# color-spu-strip-1_1-1019.net
KiCad netlist of a schematic drawn in EasyEDA Pro
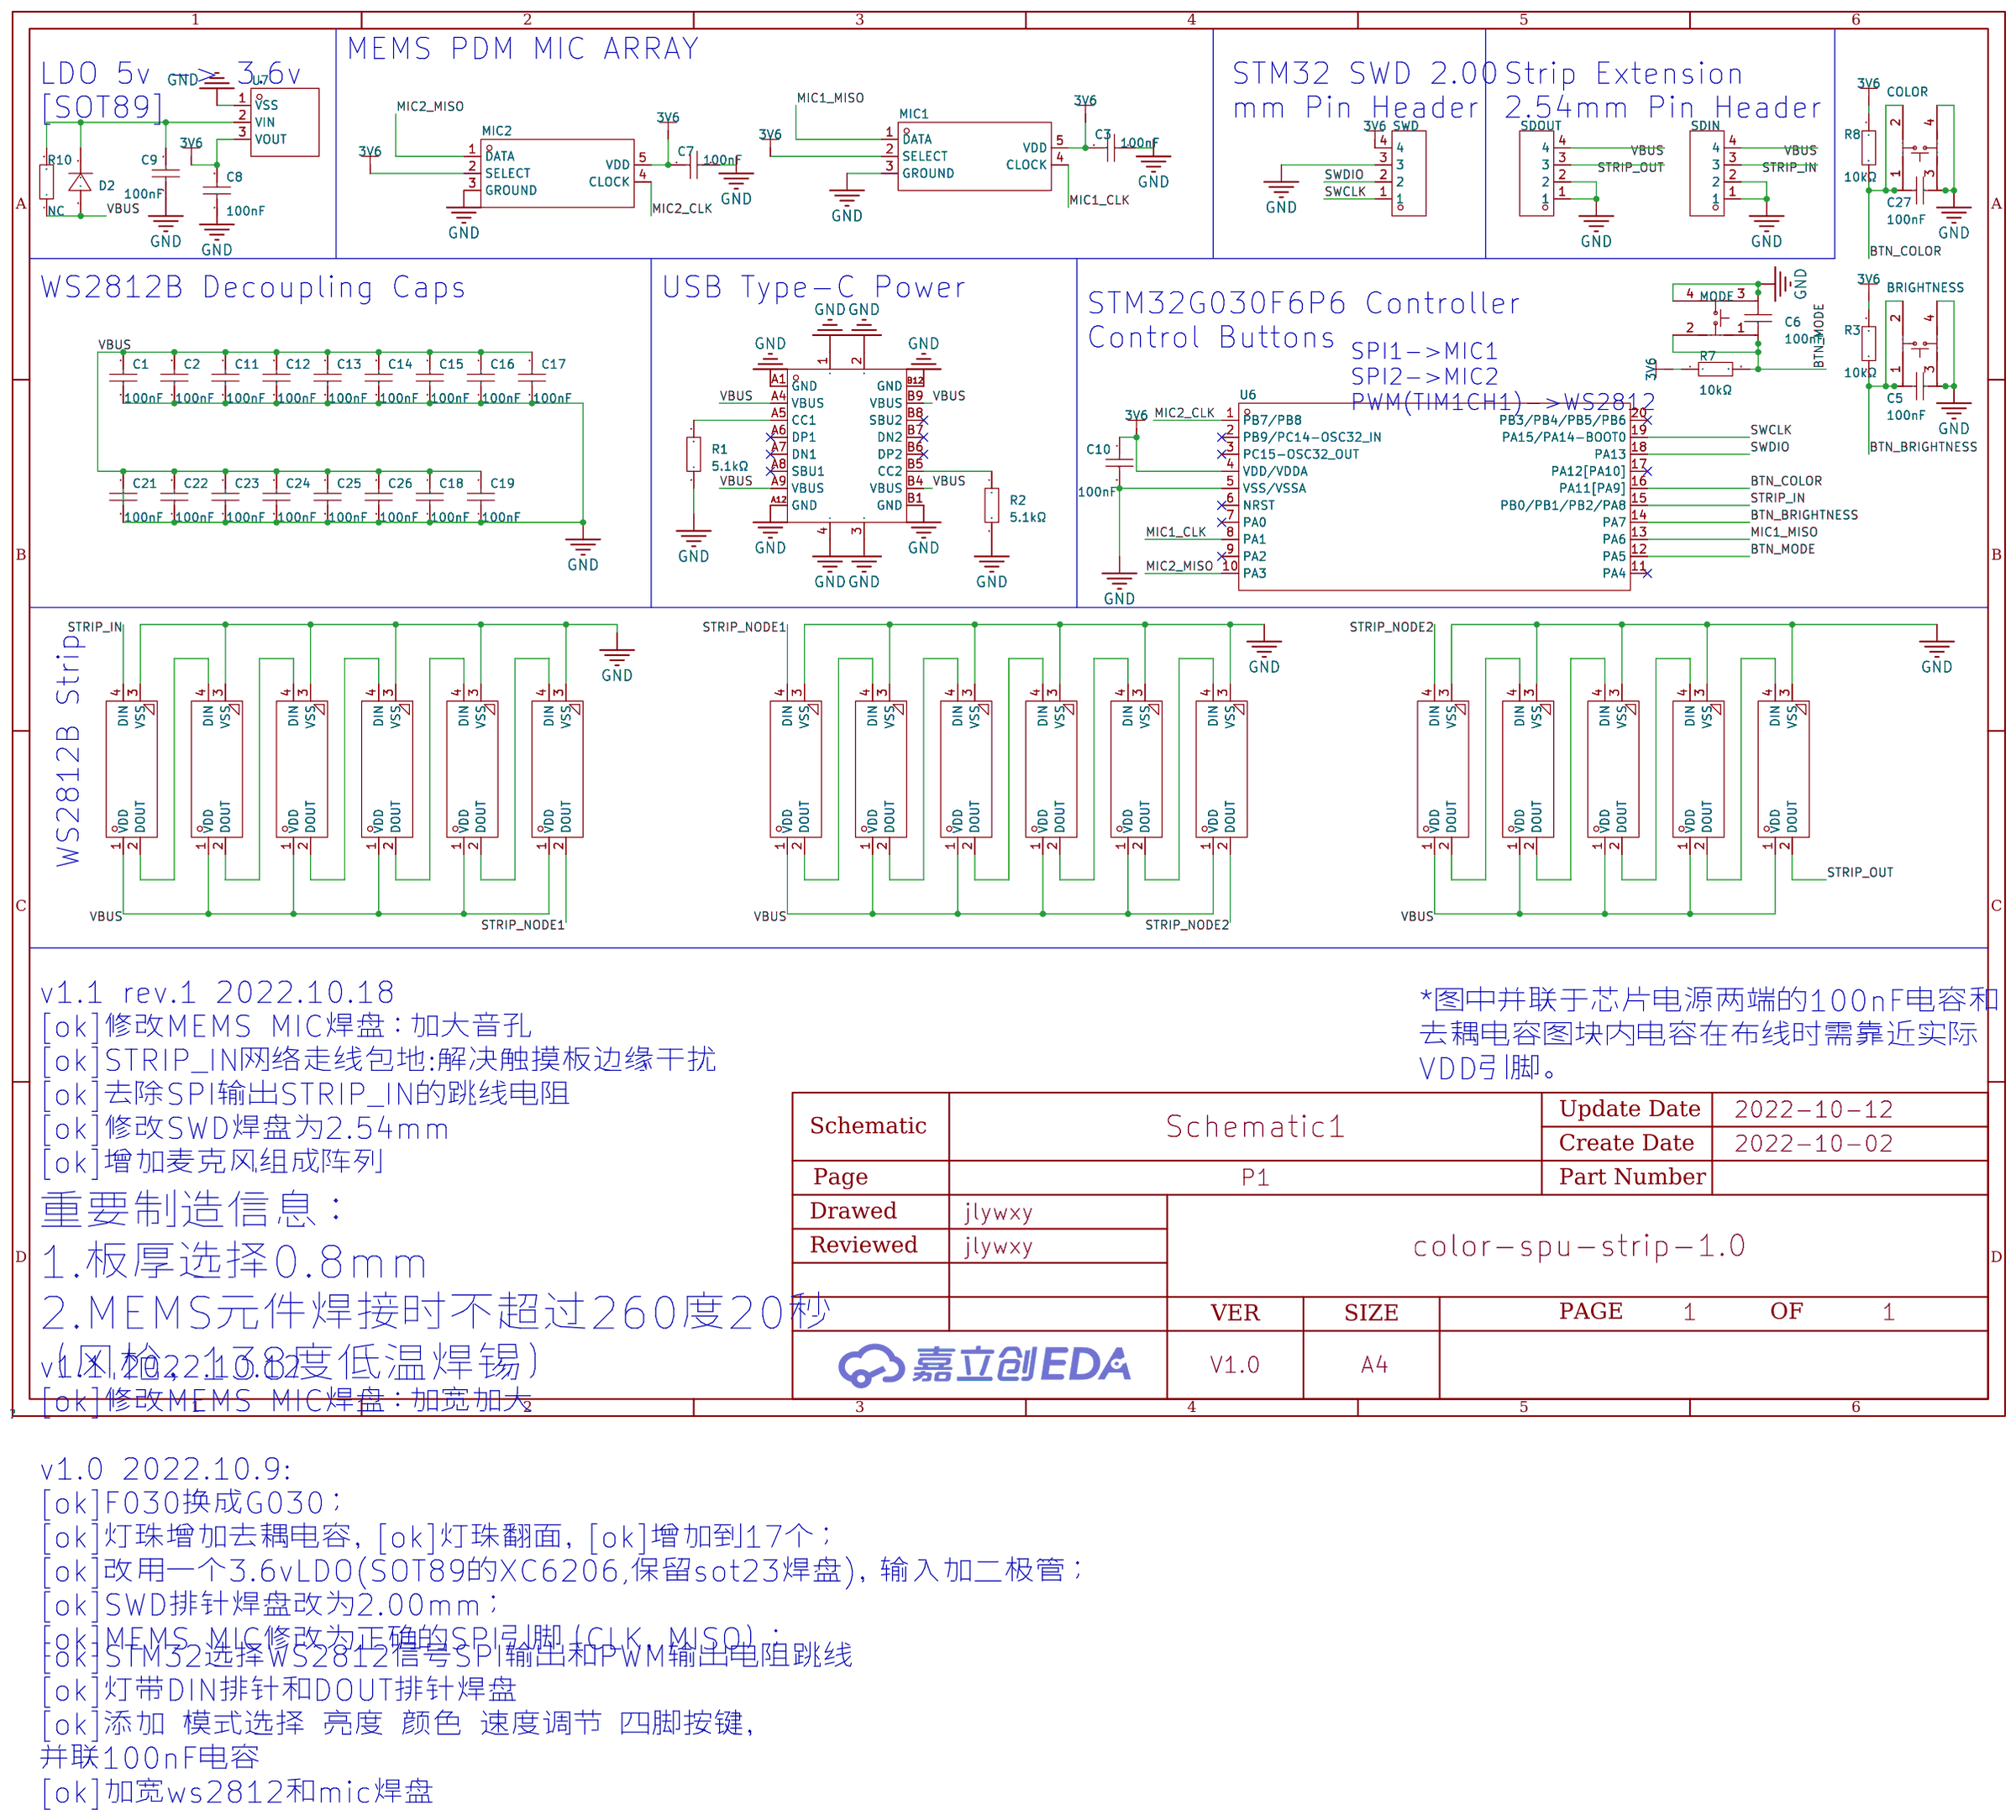
[diagram p0: schematic sheet]

(export (version "E")
  (design (tool "Eeschema 10.0.6"))
  (components
    (comp (ref "BRIGHTNESS")
      (value "SKRPABE010")
      (footprint "easyedapro:KEY-SMD_4P-L4.2-W3.2-P2.20-LS4.6")
      (description "触点电流:50mA;额定电压(DC):16V;电路结构:单刀单掷;安装方式:立贴;按钮形状:椭圆形按钮;带灯:-;开关长度:4.2mm;开关宽度:3.2mm;开关高度:2.5mm;")
      (fields (field (name "Manufacturer") "ALPSALPINE(阿尔卑斯阿尔派)"))
      (libsource (lib "easyedapro") (part "SKRPABE010"))
    )
    (comp (ref "C1")
      (value "100nF")
      (footprint "easyedapro:C0402")
      (description "容值:1uF;精度:±10%;额定电压:10V;材质(温度系数):X5R;")
      (fields
        (field (name "Manufacturer Part") "CL05A105KP5NNNC")
        (field (name "Manufacturer") "SAMSUNG(三星)")
      )
      (libsource (lib "easyedapro") (part "CL05A105KP5NNNC"))
    )
    (comp (ref "C2")
      (value "100nF")
      (footprint "easyedapro:C0402")
      (description "容值:1uF;精度:±10%;额定电压:10V;材质(温度系数):X5R;")
      (fields
        (field (name "Manufacturer Part") "CL05A105KP5NNNC")
        (field (name "Manufacturer") "SAMSUNG(三星)")
      )
      (libsource (lib "easyedapro") (part "CL05A105KP5NNNC"))
    )
    (comp (ref "C3")
      (value "100nF")
      (footprint "easyedapro:C0402")
      (description "容值:1uF;精度:±10%;额定电压:10V;材质(温度系数):X5R;")
      (fields
        (field (name "Manufacturer Part") "CL05A105KP5NNNC")
        (field (name "Manufacturer") "SAMSUNG(三星)")
      )
      (libsource (lib "easyedapro") (part "CL05A105KP5NNNC"))
    )
    (comp (ref "C5")
      (value "100nF")
      (footprint "easyedapro:C0402")
      (description "容值:1uF;精度:±10%;额定电压:10V;材质(温度系数):X5R;")
      (fields
        (field (name "Manufacturer Part") "CL05A105KP5NNNC")
        (field (name "Manufacturer") "SAMSUNG(三星)")
      )
      (libsource (lib "easyedapro") (part "CL05A105KP5NNNC"))
    )
    (comp (ref "C6")
      (value "100nF")
      (footprint "easyedapro:C0402")
      (description "容值:1uF;精度:±10%;额定电压:10V;材质(温度系数):X5R;")
      (fields
        (field (name "Manufacturer Part") "CL05A105KP5NNNC")
        (field (name "Manufacturer") "SAMSUNG(三星)")
      )
      (libsource (lib "easyedapro") (part "CL05A105KP5NNNC"))
    )
    (comp (ref "C7")
      (value "100nF")
      (footprint "easyedapro:C0402")
      (description "容值:1uF;精度:±10%;额定电压:10V;材质(温度系数):X5R;")
      (fields
        (field (name "Manufacturer Part") "CL05A105KP5NNNC")
        (field (name "Manufacturer") "SAMSUNG(三星)")
      )
      (libsource (lib "easyedapro") (part "CL05A105KP5NNNC"))
    )
    (comp (ref "C8")
      (value "100nF")
      (footprint "easyedapro:C0402")
      (description "容值:1uF;精度:±10%;额定电压:10V;材质(温度系数):X5R;")
      (fields
        (field (name "Manufacturer Part") "CL05A105KP5NNNC")
        (field (name "Manufacturer") "SAMSUNG(三星)")
      )
      (libsource (lib "easyedapro") (part "CL05A105KP5NNNC"))
    )
    (comp (ref "C9")
      (value "100nF")
      (footprint "easyedapro:C0402")
      (description "容值:1uF;精度:±10%;额定电压:10V;材质(温度系数):X5R;")
      (fields
        (field (name "Manufacturer Part") "CL05A105KP5NNNC")
        (field (name "Manufacturer") "SAMSUNG(三星)")
      )
      (libsource (lib "easyedapro") (part "CL05A105KP5NNNC"))
    )
    (comp (ref "C10")
      (value "100nF")
      (footprint "easyedapro:C0402")
      (description "容值:1uF;精度:±10%;额定电压:10V;材质(温度系数):X5R;")
      (fields
        (field (name "Manufacturer Part") "CL05A105KP5NNNC")
        (field (name "Manufacturer") "SAMSUNG(三星)")
      )
      (libsource (lib "easyedapro") (part "CL05A105KP5NNNC"))
    )
    (comp (ref "C11")
      (value "100nF")
      (footprint "easyedapro:C0402")
      (description "容值:1uF;精度:±10%;额定电压:10V;材质(温度系数):X5R;")
      (fields
        (field (name "Manufacturer Part") "CL05A105KP5NNNC")
        (field (name "Manufacturer") "SAMSUNG(三星)")
      )
      (libsource (lib "easyedapro") (part "CL05A105KP5NNNC"))
    )
    (comp (ref "C12")
      (value "100nF")
      (footprint "easyedapro:C0402")
      (description "容值:1uF;精度:±10%;额定电压:10V;材质(温度系数):X5R;")
      (fields
        (field (name "Manufacturer Part") "CL05A105KP5NNNC")
        (field (name "Manufacturer") "SAMSUNG(三星)")
      )
      (libsource (lib "easyedapro") (part "CL05A105KP5NNNC"))
    )
    (comp (ref "C13")
      (value "100nF")
      (footprint "easyedapro:C0402")
      (description "容值:1uF;精度:±10%;额定电压:10V;材质(温度系数):X5R;")
      (fields
        (field (name "Manufacturer Part") "CL05A105KP5NNNC")
        (field (name "Manufacturer") "SAMSUNG(三星)")
      )
      (libsource (lib "easyedapro") (part "CL05A105KP5NNNC"))
    )
    (comp (ref "C14")
      (value "100nF")
      (footprint "easyedapro:C0402")
      (description "容值:1uF;精度:±10%;额定电压:10V;材质(温度系数):X5R;")
      (fields
        (field (name "Manufacturer Part") "CL05A105KP5NNNC")
        (field (name "Manufacturer") "SAMSUNG(三星)")
      )
      (libsource (lib "easyedapro") (part "CL05A105KP5NNNC"))
    )
    (comp (ref "C15")
      (value "100nF")
      (footprint "easyedapro:C0402")
      (description "容值:1uF;精度:±10%;额定电压:10V;材质(温度系数):X5R;")
      (fields
        (field (name "Manufacturer Part") "CL05A105KP5NNNC")
        (field (name "Manufacturer") "SAMSUNG(三星)")
      )
      (libsource (lib "easyedapro") (part "CL05A105KP5NNNC"))
    )
    (comp (ref "C16")
      (value "100nF")
      (footprint "easyedapro:C0402")
      (description "容值:1uF;精度:±10%;额定电压:10V;材质(温度系数):X5R;")
      (fields
        (field (name "Manufacturer Part") "CL05A105KP5NNNC")
        (field (name "Manufacturer") "SAMSUNG(三星)")
      )
      (libsource (lib "easyedapro") (part "CL05A105KP5NNNC"))
    )
    (comp (ref "C17")
      (value "100nF")
      (footprint "easyedapro:C0402")
      (description "容值:1uF;精度:±10%;额定电压:10V;材质(温度系数):X5R;")
      (fields
        (field (name "Manufacturer Part") "CL05A105KP5NNNC")
        (field (name "Manufacturer") "SAMSUNG(三星)")
      )
      (libsource (lib "easyedapro") (part "CL05A105KP5NNNC"))
    )
    (comp (ref "C18")
      (value "100nF")
      (footprint "easyedapro:C0402")
      (description "容值:1uF;精度:±10%;额定电压:10V;材质(温度系数):X5R;")
      (fields
        (field (name "Manufacturer Part") "CL05A105KP5NNNC")
        (field (name "Manufacturer") "SAMSUNG(三星)")
      )
      (libsource (lib "easyedapro") (part "CL05A105KP5NNNC"))
    )
    (comp (ref "C19")
      (value "100nF")
      (footprint "easyedapro:C0402")
      (description "容值:1uF;精度:±10%;额定电压:10V;材质(温度系数):X5R;")
      (fields
        (field (name "Manufacturer Part") "CL05A105KP5NNNC")
        (field (name "Manufacturer") "SAMSUNG(三星)")
      )
      (libsource (lib "easyedapro") (part "CL05A105KP5NNNC"))
    )
    (comp (ref "C21")
      (value "100nF")
      (footprint "easyedapro:C0402")
      (description "容值:1uF;精度:±10%;额定电压:10V;材质(温度系数):X5R;")
      (fields
        (field (name "Manufacturer Part") "CL05A105KP5NNNC")
        (field (name "Manufacturer") "SAMSUNG(三星)")
      )
      (libsource (lib "easyedapro") (part "CL05A105KP5NNNC"))
    )
    (comp (ref "C22")
      (value "100nF")
      (footprint "easyedapro:C0402")
      (description "容值:1uF;精度:±10%;额定电压:10V;材质(温度系数):X5R;")
      (fields
        (field (name "Manufacturer Part") "CL05A105KP5NNNC")
        (field (name "Manufacturer") "SAMSUNG(三星)")
      )
      (libsource (lib "easyedapro") (part "CL05A105KP5NNNC"))
    )
    (comp (ref "C23")
      (value "100nF")
      (footprint "easyedapro:C0402")
      (description "容值:1uF;精度:±10%;额定电压:10V;材质(温度系数):X5R;")
      (fields
        (field (name "Manufacturer Part") "CL05A105KP5NNNC")
        (field (name "Manufacturer") "SAMSUNG(三星)")
      )
      (libsource (lib "easyedapro") (part "CL05A105KP5NNNC"))
    )
    (comp (ref "C24")
      (value "100nF")
      (footprint "easyedapro:C0402")
      (description "容值:1uF;精度:±10%;额定电压:10V;材质(温度系数):X5R;")
      (fields
        (field (name "Manufacturer Part") "CL05A105KP5NNNC")
        (field (name "Manufacturer") "SAMSUNG(三星)")
      )
      (libsource (lib "easyedapro") (part "CL05A105KP5NNNC"))
    )
    (comp (ref "C25")
      (value "100nF")
      (footprint "easyedapro:C0402")
      (description "容值:1uF;精度:±10%;额定电压:10V;材质(温度系数):X5R;")
      (fields
        (field (name "Manufacturer Part") "CL05A105KP5NNNC")
        (field (name "Manufacturer") "SAMSUNG(三星)")
      )
      (libsource (lib "easyedapro") (part "CL05A105KP5NNNC"))
    )
    (comp (ref "C26")
      (value "100nF")
      (footprint "easyedapro:C0402")
      (description "容值:1uF;精度:±10%;额定电压:10V;材质(温度系数):X5R;")
      (fields
        (field (name "Manufacturer Part") "CL05A105KP5NNNC")
        (field (name "Manufacturer") "SAMSUNG(三星)")
      )
      (libsource (lib "easyedapro") (part "CL05A105KP5NNNC"))
    )
    (comp (ref "C27")
      (value "100nF")
      (footprint "easyedapro:C0402")
      (description "容值:1uF;精度:±10%;额定电压:10V;材质(温度系数):X5R;")
      (fields
        (field (name "Manufacturer Part") "CL05A105KP5NNNC")
        (field (name "Manufacturer") "SAMSUNG(三星)")
      )
      (libsource (lib "easyedapro") (part "CL05A105KP5NNNC"))
    )
    (comp (ref "COLOR")
      (value "SKRPABE010")
      (footprint "easyedapro:KEY-SMD_4P-L4.2-W3.2-P2.20-LS4.6")
      (description "触点电流:50mA;额定电压(DC):16V;电路结构:单刀单掷;安装方式:立贴;按钮形状:椭圆形按钮;带灯:-;开关长度:4.2mm;开关宽度:3.2mm;开关高度:2.5mm;")
      (fields (field (name "Manufacturer") "ALPSALPINE(阿尔卑斯阿尔派)"))
      (libsource (lib "easyedapro") (part "SKRPABE010"))
    )
    (comp (ref "D2")
      (value "M7")
      (footprint "easyedapro:DO-214AC_L4.3-W2.7-LS5.3-RD")
      (description "二极管配置:-;直流反向耐压(Vr):1kV;平均整流电流(Io):1A;正向压降(Vf):1.1V@1A;反向电流(Ir):5A@1kV;")
      (fields (field (name "Manufacturer") "MDD"))
      (libsource (lib "easyedapro") (part "M7_C95872"))
    )
    (comp (ref "LED1")
      (value "WS2812B-B")
      (footprint "easyedapro:LED-SMD_4P-L5.0-W5.0-TL_WS2812B-B")
      (description "发光颜色:RGB三色;")
      (fields (field (name "Manufacturer") "worldsemi"))
      (libsource (lib "easyedapro") (part "WS2812B-B"))
    )
    (comp (ref "LED2")
      (value "WS2812B-B")
      (footprint "easyedapro:LED-SMD_4P-L5.0-W5.0-TL_WS2812B-B")
      (description "发光颜色:RGB三色;")
      (fields (field (name "Manufacturer") "worldsemi"))
      (libsource (lib "easyedapro") (part "WS2812B-B"))
    )
    (comp (ref "LED3")
      (value "WS2812B-B")
      (footprint "easyedapro:LED-SMD_4P-L5.0-W5.0-TL_WS2812B-B")
      (description "发光颜色:RGB三色;")
      (fields (field (name "Manufacturer") "worldsemi"))
      (libsource (lib "easyedapro") (part "WS2812B-B"))
    )
    (comp (ref "LED4")
      (value "WS2812B-B")
      (footprint "easyedapro:LED-SMD_4P-L5.0-W5.0-TL_WS2812B-B")
      (description "发光颜色:RGB三色;")
      (fields (field (name "Manufacturer") "worldsemi"))
      (libsource (lib "easyedapro") (part "WS2812B-B"))
    )
    (comp (ref "LED5")
      (value "WS2812B-B")
      (footprint "easyedapro:LED-SMD_4P-L5.0-W5.0-TL_WS2812B-B")
      (description "发光颜色:RGB三色;")
      (fields (field (name "Manufacturer") "worldsemi"))
      (libsource (lib "easyedapro") (part "WS2812B-B"))
    )
    (comp (ref "LED6")
      (value "WS2812B-B")
      (footprint "easyedapro:LED-SMD_4P-L5.0-W5.0-TL_WS2812B-B")
      (description "发光颜色:RGB三色;")
      (fields (field (name "Manufacturer") "worldsemi"))
      (libsource (lib "easyedapro") (part "WS2812B-B"))
    )
    (comp (ref "LED7")
      (value "WS2812B-B")
      (footprint "easyedapro:LED-SMD_4P-L5.0-W5.0-TL_WS2812B-B")
      (description "发光颜色:RGB三色;")
      (fields (field (name "Manufacturer") "worldsemi"))
      (libsource (lib "easyedapro") (part "WS2812B-B"))
    )
    (comp (ref "LED8")
      (value "WS2812B-B")
      (footprint "easyedapro:LED-SMD_4P-L5.0-W5.0-TL_WS2812B-B")
      (description "发光颜色:RGB三色;")
      (fields (field (name "Manufacturer") "worldsemi"))
      (libsource (lib "easyedapro") (part "WS2812B-B"))
    )
    (comp (ref "LED9")
      (value "WS2812B-B")
      (footprint "easyedapro:LED-SMD_4P-L5.0-W5.0-TL_WS2812B-B")
      (description "发光颜色:RGB三色;")
      (fields (field (name "Manufacturer") "worldsemi"))
      (libsource (lib "easyedapro") (part "WS2812B-B"))
    )
    (comp (ref "LED10")
      (value "WS2812B-B")
      (footprint "easyedapro:LED-SMD_4P-L5.0-W5.0-TL_WS2812B-B")
      (description "发光颜色:RGB三色;")
      (fields (field (name "Manufacturer") "worldsemi"))
      (libsource (lib "easyedapro") (part "WS2812B-B"))
    )
    (comp (ref "LED11")
      (value "WS2812B-B")
      (footprint "easyedapro:LED-SMD_4P-L5.0-W5.0-TL_WS2812B-B")
      (description "发光颜色:RGB三色;")
      (fields (field (name "Manufacturer") "worldsemi"))
      (libsource (lib "easyedapro") (part "WS2812B-B"))
    )
    (comp (ref "LED12")
      (value "WS2812B-B")
      (footprint "easyedapro:LED-SMD_4P-L5.0-W5.0-TL_WS2812B-B")
      (description "发光颜色:RGB三色;")
      (fields (field (name "Manufacturer") "worldsemi"))
      (libsource (lib "easyedapro") (part "WS2812B-B"))
    )
    (comp (ref "LED13")
      (value "WS2812B-B")
      (footprint "easyedapro:LED-SMD_4P-L5.0-W5.0-TL_WS2812B-B")
      (description "发光颜色:RGB三色;")
      (fields (field (name "Manufacturer") "worldsemi"))
      (libsource (lib "easyedapro") (part "WS2812B-B"))
    )
    (comp (ref "LED14")
      (value "WS2812B-B")
      (footprint "easyedapro:LED-SMD_4P-L5.0-W5.0-TL_WS2812B-B")
      (description "发光颜色:RGB三色;")
      (fields (field (name "Manufacturer") "worldsemi"))
      (libsource (lib "easyedapro") (part "WS2812B-B"))
    )
    (comp (ref "LED15")
      (value "WS2812B-B")
      (footprint "easyedapro:LED-SMD_4P-L5.0-W5.0-TL_WS2812B-B")
      (description "发光颜色:RGB三色;")
      (fields (field (name "Manufacturer") "worldsemi"))
      (libsource (lib "easyedapro") (part "WS2812B-B"))
    )
    (comp (ref "LED16")
      (value "WS2812B-B")
      (footprint "easyedapro:LED-SMD_4P-L5.0-W5.0-TL_WS2812B-B")
      (description "发光颜色:RGB三色;")
      (fields (field (name "Manufacturer") "worldsemi"))
      (libsource (lib "easyedapro") (part "WS2812B-B"))
    )
    (comp (ref "LED17")
      (value "WS2812B-B")
      (footprint "easyedapro:LED-SMD_4P-L5.0-W5.0-TL_WS2812B-B")
      (description "发光颜色:RGB三色;")
      (fields (field (name "Manufacturer") "worldsemi"))
      (libsource (lib "easyedapro") (part "WS2812B-B"))
    )
    (comp (ref "MIC1")
      (value "SPH0641LM4H-1")
      (footprint "easyedapro:MIC-SMD_5P_L3.5-W2.7-P0.82_SPH0641LU4H-1")
      (libsource (lib "easyedapro") (part "SPH0641LM4H-1"))
    )
    (comp (ref "MIC2")
      (value "SPH0641LM4H-1")
      (footprint "easyedapro:MIC-SMD_5P_L3.5-W2.7-P0.82_SPH0641LU4H-1")
      (libsource (lib "easyedapro") (part "SPH0641LM4H-1"))
    )
    (comp (ref "MODE")
      (value "SKRPABE010")
      (footprint "easyedapro:KEY-SMD_4P-L4.2-W3.2-P2.20-LS4.6")
      (description "触点电流:50mA;额定电压(DC):16V;电路结构:单刀单掷;安装方式:立贴;按钮形状:椭圆形按钮;带灯:-;开关长度:4.2mm;开关宽度:3.2mm;开关高度:2.5mm;")
      (fields (field (name "Manufacturer") "ALPSALPINE(阿尔卑斯阿尔派)"))
      (libsource (lib "easyedapro") (part "SKRPABE010"))
    )
    (comp (ref "R1")
      (value "5.1kΩ")
      (footprint "easyedapro:R0603")
      (description "电阻类型:厚膜电阻;阻值:10kΩ;精度:±1%;功率:100mW;温度系数:±100ppm/;最大工作电压:75V;工作温度范围:-55~+155;")
      (fields
        (field (name "Manufacturer Part") "0603WAF1002T5E")
        (field (name "Manufacturer") "UNI-ROYAL(厚声)")
      )
      (libsource (lib "easyedapro") (part "0603WAF1002T5E"))
    )
    (comp (ref "R2")
      (value "5.1kΩ")
      (footprint "easyedapro:R0603")
      (description "电阻类型:厚膜电阻;阻值:10kΩ;精度:±1%;功率:100mW;温度系数:±100ppm/;最大工作电压:75V;工作温度范围:-55~+155;")
      (fields
        (field (name "Manufacturer Part") "0603WAF1002T5E")
        (field (name "Manufacturer") "UNI-ROYAL(厚声)")
      )
      (libsource (lib "easyedapro") (part "0603WAF1002T5E"))
    )
    (comp (ref "R3")
      (value "10kΩ")
      (footprint "easyedapro:R0603")
      (description "电阻类型:厚膜电阻;阻值:10kΩ;精度:±1%;功率:100mW;温度系数:±100ppm/;最大工作电压:75V;工作温度范围:-55~+155;")
      (fields
        (field (name "Manufacturer Part") "0603WAF1002T5E")
        (field (name "Manufacturer") "UNI-ROYAL(厚声)")
      )
      (libsource (lib "easyedapro") (part "0603WAF1002T5E"))
    )
    (comp (ref "R7")
      (value "10kΩ")
      (footprint "easyedapro:R0603")
      (description "电阻类型:厚膜电阻;阻值:10kΩ;精度:±1%;功率:100mW;温度系数:±100ppm/;最大工作电压:75V;工作温度范围:-55~+155;")
      (fields
        (field (name "Manufacturer Part") "0603WAF1002T5E")
        (field (name "Manufacturer") "UNI-ROYAL(厚声)")
      )
      (libsource (lib "easyedapro") (part "0603WAF1002T5E"))
    )
    (comp (ref "R8")
      (value "10kΩ")
      (footprint "easyedapro:R0603")
      (description "电阻类型:厚膜电阻;阻值:10kΩ;精度:±1%;功率:100mW;温度系数:±100ppm/;最大工作电压:75V;工作温度范围:-55~+155;")
      (fields
        (field (name "Manufacturer Part") "0603WAF1002T5E")
        (field (name "Manufacturer") "UNI-ROYAL(厚声)")
      )
      (libsource (lib "easyedapro") (part "0603WAF1002T5E"))
    )
    (comp (ref "R10")
      (value "NC")
      (footprint "easyedapro:R0603")
      (description "电阻类型:厚膜电阻;阻值:10kΩ;精度:±1%;功率:100mW;温度系数:±100ppm/;最大工作电压:75V;工作温度范围:-55~+155;")
      (fields
        (field (name "Manufacturer Part") "0603WAF1002T5E")
        (field (name "Manufacturer") "UNI-ROYAL(厚声)")
      )
      (libsource (lib "easyedapro") (part "0603WAF1002T5E"))
    )
    (comp (ref "SDIN")
      (value "M2510V-04P")
      (footprint "easyedapro:CONN-TH_M2510V-04P")
      (description "参考系列:-;间距:2.54mm;插针结构:1x4P;排数:1;每排PIN数:4;行距:-;公母:公型插针;安装方式:直插;额定电流:3A;工作温度范围:-25~+85;")
      (fields (field (name "Manufacturer") "XFCN(台湾兴飞)"))
      (libsource (lib "easyedapro") (part "M2510V-04P"))
    )
    (comp (ref "SDOUT")
      (value "M2510V-04P")
      (footprint "easyedapro:CONN-TH_M2510V-04P")
      (description "参考系列:-;间距:2.54mm;插针结构:1x4P;排数:1;每排PIN数:4;行距:-;公母:公型插针;安装方式:直插;额定电流:3A;工作温度范围:-25~+85;")
      (fields (field (name "Manufacturer") "XFCN(台湾兴飞)"))
      (libsource (lib "easyedapro") (part "M2510V-04P"))
    )
    (comp (ref "SWD")
      (value "M2510V-04P")
      (footprint "easyedapro:CONN-TH_M2510V-04P")
      (description "参考系列:-;间距:2.54mm;插针结构:1x4P;排数:1;每排PIN数:4;行距:-;公母:公型插针;安装方式:直插;额定电流:3A;工作温度范围:-25~+85;")
      (fields (field (name "Manufacturer") "XFCN(台湾兴飞)"))
      (libsource (lib "easyedapro") (part "M2510V-04P"))
    )
    (comp (ref "U2")
      (value "20009-UCAF001-X")
      (footprint "easyedapro:TYPE-C-SMD_20009-UCAF001-X")
      (description "TYPE C 16P母座板上 L=8.30")
      (fields (field (name "Manufacturer") "MINTRON(明硕)"))
      (libsource (lib "easyedapro") (part "20009-UCAF001-X"))
    )
    (comp (ref "U6")
      (value "STM32G030F6P6")
      (footprint "easyedapro:TSSOP-20_L6.5-W4.4-P0.65-LS6.4-BL")
      (description "CPU位数:-;ROM类型:-;CPU内核:-;主频（MAX):-;工作电压:-;")
      (fields (field (name "Manufacturer") "ST(意法半导体)"))
      (libsource (lib "easyedapro") (part "STM32G030F6P6"))
    )
    (comp (ref "U7")
      (value "XC6206P362PR")
      (footprint "easyedapro:SOT-89-3_L4.5-W2.5-P1.50-LS4.2-BR")
      (description "输出类型:-;")
      (fields (field (name "Manufacturer") "UMW(友台半导体)"))
      (libsource (lib "easyedapro") (part "XC6206P362PR"))
    )
  )
  (nets
    (net (code "1") (name "/BTN_BRIGHTNESS") (class "Default")
      (node (ref "BRIGHTNESS") (pin "1") (pinfunction "1_1") (pintype "input"))
      (node (ref "BRIGHTNESS") (pin "2") (pinfunction "2_2") (pintype "input"))
      (node (ref "C5") (pin "2") (pinfunction "2_2") (pintype "input"))
      (node (ref "R3") (pin "2") (pinfunction "2_2") (pintype "input"))
      (node (ref "U6") (pin "14") (pinfunction "PA7_14") (pintype "input"))
    )
    (net (code "2") (name "/BTN_COLOR") (class "Default")
      (node (ref "C27") (pin "2") (pinfunction "2_2") (pintype "input"))
      (node (ref "COLOR") (pin "1") (pinfunction "1_1") (pintype "input"))
      (node (ref "COLOR") (pin "2") (pinfunction "2_2") (pintype "input"))
      (node (ref "R8") (pin "2") (pinfunction "2_2") (pintype "input"))
      (node (ref "U6") (pin "16") (pinfunction "PA11[PA9]_16") (pintype "input"))
    )
    (net (code "3") (name "/BTN_MODE") (class "Default")
      (node (ref "C6") (pin "2") (pinfunction "2_2") (pintype "input"))
      (node (ref "MODE") (pin "1") (pinfunction "1_1") (pintype "input"))
      (node (ref "MODE") (pin "2") (pinfunction "2_2") (pintype "input"))
      (node (ref "R7") (pin "2") (pinfunction "2_2") (pintype "input"))
      (node (ref "U6") (pin "12") (pinfunction "PA5_12") (pintype "input"))
    )
    (net (code "4") (name "/MIC1_CLK") (class "Default")
      (node (ref "MIC1") (pin "4") (pinfunction "CLOCK_4") (pintype "input"))
      (node (ref "U6") (pin "8") (pinfunction "PA1_8") (pintype "input"))
    )
    (net (code "5") (name "/MIC1_MISO") (class "Default")
      (node (ref "MIC1") (pin "1") (pinfunction "DATA_1") (pintype "input"))
      (node (ref "U6") (pin "13") (pinfunction "PA6_13") (pintype "input"))
    )
    (net (code "6") (name "/MIC2_CLK") (class "Default")
      (node (ref "MIC2") (pin "4") (pinfunction "CLOCK_4") (pintype "input"))
      (node (ref "U6") (pin "1") (pinfunction "PB7/PB8_1") (pintype "input"))
    )
    (net (code "7") (name "/MIC2_MISO") (class "Default")
      (node (ref "MIC2") (pin "1") (pinfunction "DATA_1") (pintype "input"))
      (node (ref "U6") (pin "10") (pinfunction "PA3_10") (pintype "input"))
    )
    (net (code "8") (name "/STRIP_IN") (class "Default")
      (node (ref "LED1") (pin "4") (pinfunction "DIN_4") (pintype "input"))
      (node (ref "SDIN") (pin "3") (pinfunction "3_3") (pintype "input"))
      (node (ref "U6") (pin "15") (pinfunction "PB0/PB1/PB2/PA8_15") (pintype "input"))
    )
    (net (code "9") (name "/STRIP_NODE1") (class "Default")
      (node (ref "LED6") (pin "2") (pinfunction "DOUT_2") (pintype "input"))
      (node (ref "LED7") (pin "4") (pinfunction "DIN_4") (pintype "input"))
    )
    (net (code "10") (name "/STRIP_NODE2") (class "Default")
      (node (ref "LED12") (pin "2") (pinfunction "DOUT_2") (pintype "input"))
      (node (ref "LED13") (pin "4") (pinfunction "DIN_4") (pintype "input"))
    )
    (net (code "11") (name "/STRIP_OUT") (class "Default")
      (node (ref "LED17") (pin "2") (pinfunction "DOUT_2") (pintype "input"))
      (node (ref "SDOUT") (pin "3") (pinfunction "3_3") (pintype "input"))
    )
    (net (code "12") (name "/SWCLK") (class "Default")
      (node (ref "SWD") (pin "1") (pinfunction "1_1") (pintype "input"))
      (node (ref "U6") (pin "19") (pinfunction "PA15/PA14-BOOT0_19") (pintype "input"))
    )
    (net (code "13") (name "/SWDIO") (class "Default")
      (node (ref "SWD") (pin "2") (pinfunction "2_2") (pintype "input"))
      (node (ref "U6") (pin "18") (pinfunction "PA13_18") (pintype "input"))
    )
    (net (code "14") (name "/VBUS") (class "Default")
      (node (ref "C1") (pin "2") (pinfunction "2_2") (pintype "input"))
      (node (ref "C11") (pin "2") (pinfunction "2_2") (pintype "input"))
      (node (ref "C12") (pin "2") (pinfunction "2_2") (pintype "input"))
      (node (ref "C13") (pin "2") (pinfunction "2_2") (pintype "input"))
      (node (ref "C14") (pin "2") (pinfunction "2_2") (pintype "input"))
      (node (ref "C15") (pin "2") (pinfunction "2_2") (pintype "input"))
      (node (ref "C16") (pin "2") (pinfunction "2_2") (pintype "input"))
      (node (ref "C17") (pin "2") (pinfunction "2_2") (pintype "input"))
      (node (ref "C18") (pin "2") (pinfunction "2_2") (pintype "input"))
      (node (ref "C19") (pin "2") (pinfunction "2_2") (pintype "input"))
      (node (ref "C2") (pin "2") (pinfunction "2_2") (pintype "input"))
      (node (ref "C21") (pin "2") (pinfunction "2_2") (pintype "input"))
      (node (ref "C22") (pin "2") (pinfunction "2_2") (pintype "input"))
      (node (ref "C23") (pin "2") (pinfunction "2_2") (pintype "input"))
      (node (ref "C24") (pin "2") (pinfunction "2_2") (pintype "input"))
      (node (ref "C25") (pin "2") (pinfunction "2_2") (pintype "input"))
      (node (ref "C26") (pin "2") (pinfunction "2_2") (pintype "input"))
      (node (ref "D2") (pin "2") (pinfunction "A_2") (pintype "input"))
      (node (ref "LED1") (pin "1") (pinfunction "VDD_1") (pintype "input"))
      (node (ref "LED10") (pin "1") (pinfunction "VDD_1") (pintype "input"))
      (node (ref "LED11") (pin "1") (pinfunction "VDD_1") (pintype "input"))
      (node (ref "LED12") (pin "1") (pinfunction "VDD_1") (pintype "input"))
      (node (ref "LED13") (pin "1") (pinfunction "VDD_1") (pintype "input"))
      (node (ref "LED14") (pin "1") (pinfunction "VDD_1") (pintype "input"))
      (node (ref "LED15") (pin "1") (pinfunction "VDD_1") (pintype "input"))
      (node (ref "LED16") (pin "1") (pinfunction "VDD_1") (pintype "input"))
      (node (ref "LED17") (pin "1") (pinfunction "VDD_1") (pintype "input"))
      (node (ref "LED2") (pin "1") (pinfunction "VDD_1") (pintype "input"))
      (node (ref "LED3") (pin "1") (pinfunction "VDD_1") (pintype "input"))
      (node (ref "LED4") (pin "1") (pinfunction "VDD_1") (pintype "input"))
      (node (ref "LED5") (pin "1") (pinfunction "VDD_1") (pintype "input"))
      (node (ref "LED6") (pin "1") (pinfunction "VDD_1") (pintype "input"))
      (node (ref "LED7") (pin "1") (pinfunction "VDD_1") (pintype "input"))
      (node (ref "LED8") (pin "1") (pinfunction "VDD_1") (pintype "input"))
      (node (ref "LED9") (pin "1") (pinfunction "VDD_1") (pintype "input"))
      (node (ref "R10") (pin "1") (pinfunction "1_1") (pintype "input"))
      (node (ref "SDIN") (pin "4") (pinfunction "4_4") (pintype "input"))
      (node (ref "SDOUT") (pin "4") (pinfunction "4_4") (pintype "input"))
      (node (ref "U2") (pin "A4") (pinfunction "VBUS_A4") (pintype "input"))
      (node (ref "U2") (pin "A9") (pinfunction "VBUS_A9") (pintype "input"))
      (node (ref "U2") (pin "B4") (pinfunction "VBUS_B4") (pintype "input"))
      (node (ref "U2") (pin "B9") (pinfunction "VBUS_B9") (pintype "input"))
    )
    (net (code "15") (name "3V6") (class "Default")
      (node (ref "C10") (pin "1") (pinfunction "1_1") (pintype "input"))
      (node (ref "C3") (pin "2") (pinfunction "2_2") (pintype "input"))
      (node (ref "C7") (pin "2") (pinfunction "2_2") (pintype "input"))
      (node (ref "C8") (pin "2") (pinfunction "2_2") (pintype "input"))
      (node (ref "MIC1") (pin "2") (pinfunction "SELECT_2") (pintype "input"))
      (node (ref "MIC1") (pin "5") (pinfunction "VDD_5") (pintype "input"))
      (node (ref "MIC2") (pin "2") (pinfunction "SELECT_2") (pintype "input"))
      (node (ref "MIC2") (pin "5") (pinfunction "VDD_5") (pintype "input"))
      (node (ref "R3") (pin "1") (pinfunction "1_1") (pintype "input"))
      (node (ref "R7") (pin "1") (pinfunction "1_1") (pintype "input"))
      (node (ref "R8") (pin "1") (pinfunction "1_1") (pintype "input"))
      (node (ref "SWD") (pin "4") (pinfunction "4_4") (pintype "input"))
      (node (ref "U6") (pin "4") (pinfunction "VDD/VDDA_4") (pintype "input"))
      (node (ref "U7") (pin "3") (pinfunction "VOUT_3") (pintype "input"))
    )
    (net (code "16") (name "GND") (class "Default")
      (node (ref "BRIGHTNESS") (pin "3") (pinfunction "3_3") (pintype "input"))
      (node (ref "BRIGHTNESS") (pin "4") (pinfunction "4_4") (pintype "input"))
      (node (ref "C1") (pin "1") (pinfunction "1_1") (pintype "input"))
      (node (ref "C10") (pin "2") (pinfunction "2_2") (pintype "input"))
      (node (ref "C11") (pin "1") (pinfunction "1_1") (pintype "input"))
      (node (ref "C12") (pin "1") (pinfunction "1_1") (pintype "input"))
      (node (ref "C13") (pin "1") (pinfunction "1_1") (pintype "input"))
      (node (ref "C14") (pin "1") (pinfunction "1_1") (pintype "input"))
      (node (ref "C15") (pin "1") (pinfunction "1_1") (pintype "input"))
      (node (ref "C16") (pin "1") (pinfunction "1_1") (pintype "input"))
      (node (ref "C17") (pin "1") (pinfunction "1_1") (pintype "input"))
      (node (ref "C18") (pin "1") (pinfunction "1_1") (pintype "input"))
      (node (ref "C19") (pin "1") (pinfunction "1_1") (pintype "input"))
      (node (ref "C2") (pin "1") (pinfunction "1_1") (pintype "input"))
      (node (ref "C21") (pin "1") (pinfunction "1_1") (pintype "input"))
      (node (ref "C22") (pin "1") (pinfunction "1_1") (pintype "input"))
      (node (ref "C23") (pin "1") (pinfunction "1_1") (pintype "input"))
      (node (ref "C24") (pin "1") (pinfunction "1_1") (pintype "input"))
      (node (ref "C25") (pin "1") (pinfunction "1_1") (pintype "input"))
      (node (ref "C26") (pin "1") (pinfunction "1_1") (pintype "input"))
      (node (ref "C27") (pin "1") (pinfunction "1_1") (pintype "input"))
      (node (ref "C3") (pin "1") (pinfunction "1_1") (pintype "input"))
      (node (ref "C5") (pin "1") (pinfunction "1_1") (pintype "input"))
      (node (ref "C6") (pin "1") (pinfunction "1_1") (pintype "input"))
      (node (ref "C7") (pin "1") (pinfunction "1_1") (pintype "input"))
      (node (ref "C8") (pin "1") (pinfunction "1_1") (pintype "input"))
      (node (ref "C9") (pin "1") (pinfunction "1_1") (pintype "input"))
      (node (ref "COLOR") (pin "3") (pinfunction "3_3") (pintype "input"))
      (node (ref "COLOR") (pin "4") (pinfunction "4_4") (pintype "input"))
      (node (ref "LED1") (pin "3") (pinfunction "VSS_3") (pintype "input"))
      (node (ref "LED10") (pin "3") (pinfunction "VSS_3") (pintype "input"))
      (node (ref "LED11") (pin "3") (pinfunction "VSS_3") (pintype "input"))
      (node (ref "LED12") (pin "3") (pinfunction "VSS_3") (pintype "input"))
      (node (ref "LED13") (pin "3") (pinfunction "VSS_3") (pintype "input"))
      (node (ref "LED14") (pin "3") (pinfunction "VSS_3") (pintype "input"))
      (node (ref "LED15") (pin "3") (pinfunction "VSS_3") (pintype "input"))
      (node (ref "LED16") (pin "3") (pinfunction "VSS_3") (pintype "input"))
      (node (ref "LED17") (pin "3") (pinfunction "VSS_3") (pintype "input"))
      (node (ref "LED2") (pin "3") (pinfunction "VSS_3") (pintype "input"))
      (node (ref "LED3") (pin "3") (pinfunction "VSS_3") (pintype "input"))
      (node (ref "LED4") (pin "3") (pinfunction "VSS_3") (pintype "input"))
      (node (ref "LED5") (pin "3") (pinfunction "VSS_3") (pintype "input"))
      (node (ref "LED6") (pin "3") (pinfunction "VSS_3") (pintype "input"))
      (node (ref "LED7") (pin "3") (pinfunction "VSS_3") (pintype "input"))
      (node (ref "LED8") (pin "3") (pinfunction "VSS_3") (pintype "input"))
      (node (ref "LED9") (pin "3") (pinfunction "VSS_3") (pintype "input"))
      (node (ref "MIC1") (pin "3") (pinfunction "GROUND_3") (pintype "input"))
      (node (ref "MIC2") (pin "3") (pinfunction "GROUND_3") (pintype "input"))
      (node (ref "MODE") (pin "3") (pinfunction "3_3") (pintype "input"))
      (node (ref "MODE") (pin "4") (pinfunction "4_4") (pintype "input"))
      (node (ref "R1") (pin "1") (pinfunction "1_1") (pintype "input"))
      (node (ref "R2") (pin "2") (pinfunction "2_2") (pintype "input"))
      (node (ref "SDIN") (pin "1") (pinfunction "1_1") (pintype "input"))
      (node (ref "SDIN") (pin "2") (pinfunction "2_2") (pintype "input"))
      (node (ref "SDOUT") (pin "1") (pinfunction "1_1") (pintype "input"))
      (node (ref "SDOUT") (pin "2") (pinfunction "2_2") (pintype "input"))
      (node (ref "SWD") (pin "3") (pinfunction "3_3") (pintype "input"))
      (node (ref "U2") (pin "1") (pinfunction "1_1") (pintype "input"))
      (node (ref "U2") (pin "2") (pinfunction "2_2") (pintype "input"))
      (node (ref "U2") (pin "3") (pinfunction "3_3") (pintype "input"))
      (node (ref "U2") (pin "4") (pinfunction "4_4") (pintype "input"))
      (node (ref "U2") (pin "A1") (pinfunction "GND_A1") (pintype "input"))
      (node (ref "U2") (pin "A12") (pinfunction "GND_A12") (pintype "input"))
      (node (ref "U2") (pin "B1") (pinfunction "GND_B1") (pintype "input"))
      (node (ref "U2") (pin "B12") (pinfunction "GND_B12") (pintype "input"))
      (node (ref "U6") (pin "5") (pinfunction "VSS/VSSA_5") (pintype "input"))
      (node (ref "U7") (pin "1") (pinfunction "VSS_1") (pintype "input"))
    )
    (net (code "17") (name "Net-(D2-K)") (class "Default")
      (node (ref "C9") (pin "2") (pinfunction "2_2") (pintype "input"))
      (node (ref "D2") (pin "1") (pinfunction "K_1") (pintype "input"))
      (node (ref "R10") (pin "2") (pinfunction "2_2") (pintype "input"))
      (node (ref "U7") (pin "2") (pinfunction "VIN_2") (pintype "input"))
    )
    (net (code "18") (name "Net-(LED1-DOUT)") (class "Default")
      (node (ref "LED1") (pin "2") (pinfunction "DOUT_2") (pintype "input"))
      (node (ref "LED2") (pin "4") (pinfunction "DIN_4") (pintype "input"))
    )
    (net (code "19") (name "Net-(LED2-DOUT)") (class "Default")
      (node (ref "LED2") (pin "2") (pinfunction "DOUT_2") (pintype "input"))
      (node (ref "LED3") (pin "4") (pinfunction "DIN_4") (pintype "input"))
    )
    (net (code "20") (name "Net-(LED3-DOUT)") (class "Default")
      (node (ref "LED3") (pin "2") (pinfunction "DOUT_2") (pintype "input"))
      (node (ref "LED4") (pin "4") (pinfunction "DIN_4") (pintype "input"))
    )
    (net (code "21") (name "Net-(LED4-DOUT)") (class "Default")
      (node (ref "LED4") (pin "2") (pinfunction "DOUT_2") (pintype "input"))
      (node (ref "LED5") (pin "4") (pinfunction "DIN_4") (pintype "input"))
    )
    (net (code "22") (name "Net-(LED5-DOUT)") (class "Default")
      (node (ref "LED5") (pin "2") (pinfunction "DOUT_2") (pintype "input"))
      (node (ref "LED6") (pin "4") (pinfunction "DIN_4") (pintype "input"))
    )
    (net (code "23") (name "Net-(LED7-DOUT)") (class "Default")
      (node (ref "LED7") (pin "2") (pinfunction "DOUT_2") (pintype "input"))
      (node (ref "LED8") (pin "4") (pinfunction "DIN_4") (pintype "input"))
    )
    (net (code "24") (name "Net-(LED8-DOUT)") (class "Default")
      (node (ref "LED8") (pin "2") (pinfunction "DOUT_2") (pintype "input"))
      (node (ref "LED9") (pin "4") (pinfunction "DIN_4") (pintype "input"))
    )
    (net (code "25") (name "Net-(LED10-DIN)") (class "Default")
      (node (ref "LED10") (pin "4") (pinfunction "DIN_4") (pintype "input"))
      (node (ref "LED9") (pin "2") (pinfunction "DOUT_2") (pintype "input"))
    )
    (net (code "26") (name "Net-(LED10-DOUT)") (class "Default")
      (node (ref "LED10") (pin "2") (pinfunction "DOUT_2") (pintype "input"))
      (node (ref "LED11") (pin "4") (pinfunction "DIN_4") (pintype "input"))
    )
    (net (code "27") (name "Net-(LED11-DOUT)") (class "Default")
      (node (ref "LED11") (pin "2") (pinfunction "DOUT_2") (pintype "input"))
      (node (ref "LED12") (pin "4") (pinfunction "DIN_4") (pintype "input"))
    )
    (net (code "28") (name "Net-(LED13-DOUT)") (class "Default")
      (node (ref "LED13") (pin "2") (pinfunction "DOUT_2") (pintype "input"))
      (node (ref "LED14") (pin "4") (pinfunction "DIN_4") (pintype "input"))
    )
    (net (code "29") (name "Net-(LED14-DOUT)") (class "Default")
      (node (ref "LED14") (pin "2") (pinfunction "DOUT_2") (pintype "input"))
      (node (ref "LED15") (pin "4") (pinfunction "DIN_4") (pintype "input"))
    )
    (net (code "30") (name "Net-(LED15-DOUT)") (class "Default")
      (node (ref "LED15") (pin "2") (pinfunction "DOUT_2") (pintype "input"))
      (node (ref "LED16") (pin "4") (pinfunction "DIN_4") (pintype "input"))
    )
    (net (code "31") (name "Net-(LED16-DOUT)") (class "Default")
      (node (ref "LED16") (pin "2") (pinfunction "DOUT_2") (pintype "input"))
      (node (ref "LED17") (pin "4") (pinfunction "DIN_4") (pintype "input"))
    )
    (net (code "32") (name "Net-(U2-CC1)") (class "Default")
      (node (ref "R1") (pin "2") (pinfunction "2_2") (pintype "input"))
      (node (ref "U2") (pin "A5") (pinfunction "CC1_A5") (pintype "input"))
    )
    (net (code "33") (name "Net-(U2-CC2)") (class "Default")
      (node (ref "R2") (pin "1") (pinfunction "1_1") (pintype "input"))
      (node (ref "U2") (pin "B5") (pinfunction "CC2_B5") (pintype "input"))
    )
    (net (code "34") (name "unconnected-(U2-DN1-PadA7)") (class "Default")
      (node (ref "U2") (pin "A7") (pinfunction "DN1_A7") (pintype "input+no_connect"))
    )
    (net (code "35") (name "unconnected-(U2-DN2-PadB7)") (class "Default")
      (node (ref "U2") (pin "B7") (pinfunction "DN2_B7") (pintype "input+no_connect"))
    )
    (net (code "36") (name "unconnected-(U2-DP1-PadA6)") (class "Default")
      (node (ref "U2") (pin "A6") (pinfunction "DP1_A6") (pintype "input+no_connect"))
    )
    (net (code "37") (name "unconnected-(U2-DP2-PadB6)") (class "Default")
      (node (ref "U2") (pin "B6") (pinfunction "DP2_B6") (pintype "input+no_connect"))
    )
    (net (code "38") (name "unconnected-(U2-SBU1-PadA8)") (class "Default")
      (node (ref "U2") (pin "A8") (pinfunction "SBU1_A8") (pintype "input+no_connect"))
    )
    (net (code "39") (name "unconnected-(U2-SBU2-PadB8)") (class "Default")
      (node (ref "U2") (pin "B8") (pinfunction "SBU2_B8") (pintype "input+no_connect"))
    )
    (net (code "40") (name "unconnected-(U6-NRST-Pad6)") (class "Default")
      (node (ref "U6") (pin "6") (pinfunction "NRST_6") (pintype "input+no_connect"))
    )
    (net (code "41") (name "unconnected-(U6-PA0-Pad7)") (class "Default")
      (node (ref "U6") (pin "7") (pinfunction "PA0_7") (pintype "input+no_connect"))
    )
    (net (code "42") (name "unconnected-(U6-PA2-Pad9)") (class "Default")
      (node (ref "U6") (pin "9") (pinfunction "PA2_9") (pintype "input+no_connect"))
    )
    (net (code "43") (name "unconnected-(U6-PA4-Pad11)") (class "Default")
      (node (ref "U6") (pin "11") (pinfunction "PA4_11") (pintype "input+no_connect"))
    )
    (net (code "44") (name "unconnected-(U6-PA12[PA10]-Pad17)") (class "Default")
      (node (ref "U6") (pin "17") (pinfunction "PA12[PA10]_17") (pintype "input+no_connect"))
    )
    (net (code "45") (name "unconnected-(U6-PB3{slash}PB4{slash}PB5{slash}PB6-Pad20)") (class "Default")
      (node (ref "U6") (pin "20") (pinfunction "PB3/PB4/PB5/PB6_20") (pintype "input+no_connect"))
    )
    (net (code "46") (name "unconnected-(U6-PB9{slash}PC14-OSC32_IN-Pad2)") (class "Default")
      (node (ref "U6") (pin "2") (pinfunction "PB9/PC14-OSC32_IN_2") (pintype "input+no_connect"))
    )
    (net (code "47") (name "unconnected-(U6-PC15-OSC32_OUT-Pad3)") (class "Default")
      (node (ref "U6") (pin "3") (pinfunction "PC15-OSC32_OUT_3") (pintype "input+no_connect"))
    )
  )
)
